# M0_Express_eh_shield.net
KiCad netlist of a schematic drawn in EAGLE
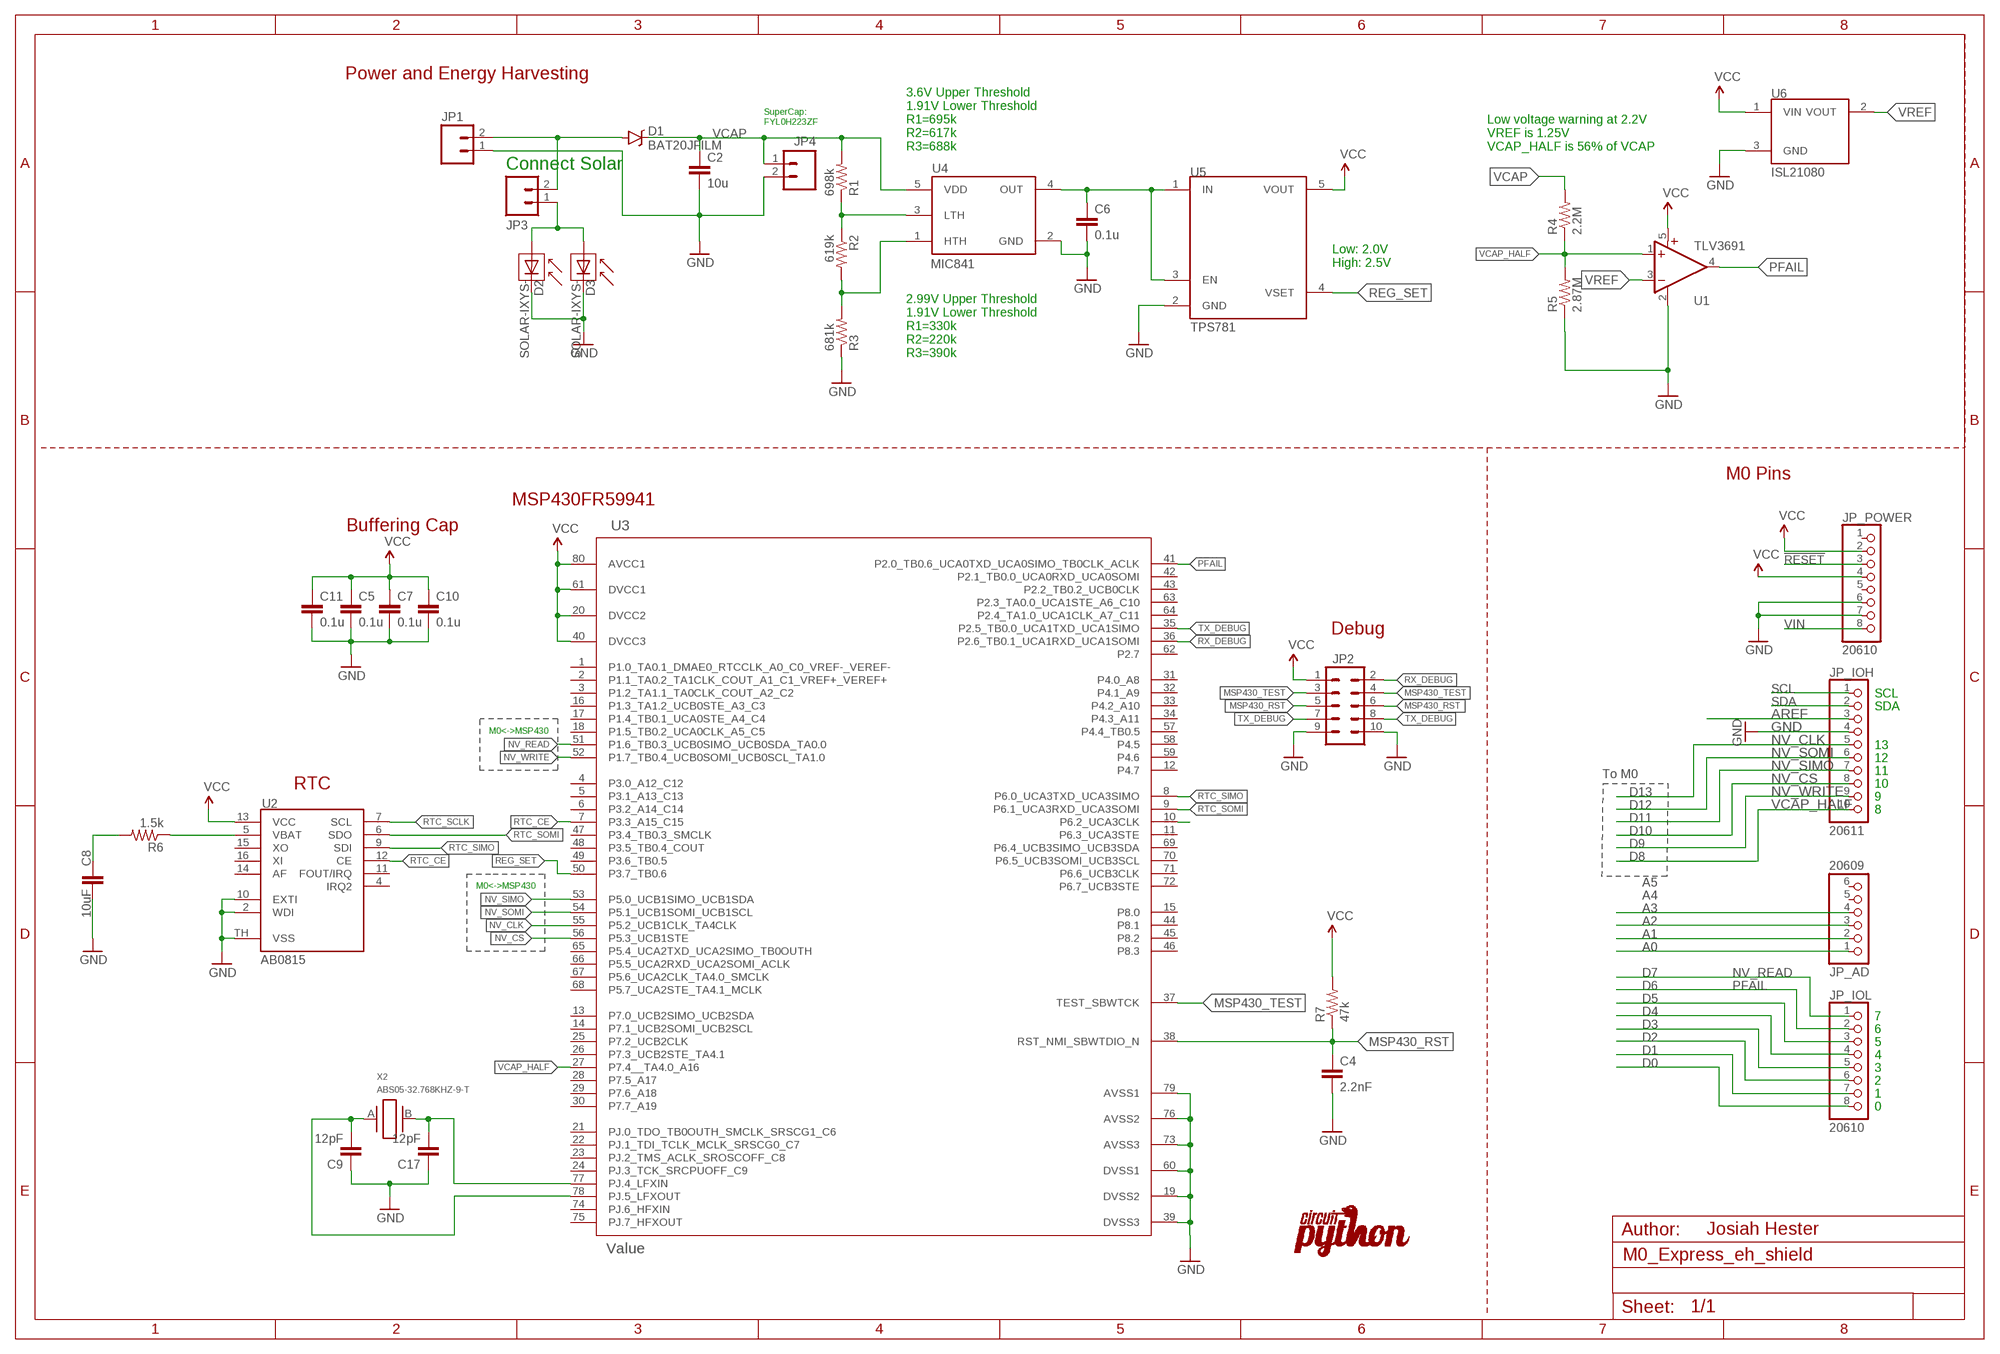
[diagram p0: schematic, sheet 1]

(export (version "E")
  (design (tool "Eeschema 10.0.6"))
  (components
    (comp (ref "C2")
      (value "10u")
      (footprint "eagle-import:0805")
      (libsource (lib "eagle-import") (part "CAP0805"))
    )
    (comp (ref "C4")
      (value "2.2nF")
      (footprint "eagle-import:0603")
      (fields (field (name "MPN") "  06035C222KAT2A"))
      (libsource (lib "eagle-import") (part "C-EU0603"))
    )
    (comp (ref "C5")
      (value "0.1u")
      (footprint "eagle-import:0603")
      (fields (field (name "MPN") "CL10B104KO8NNNC "))
      (libsource (lib "eagle-import") (part "C-EU0603"))
    )
    (comp (ref "C6")
      (value "0.1u")
      (footprint "eagle-import:0603")
      (fields (field (name "MPN") "CL10B104KO8NNNC "))
      (libsource (lib "eagle-import") (part "C-EU0603"))
    )
    (comp (ref "C7")
      (value "0.1u")
      (footprint "eagle-import:0603")
      (fields (field (name "MPN") "CL10B104KO8NNNC "))
      (libsource (lib "eagle-import") (part "C-EU0603"))
    )
    (comp (ref "C8")
      (value "10uF")
      (footprint "eagle-import:0805")
      (libsource (lib "eagle-import") (part "CAP0805"))
    )
    (comp (ref "C9")
      (value "12pF")
      (footprint "eagle-import:0603")
      (fields (field (name "MPN") "CL10C120JB8NNNC"))
      (libsource (lib "eagle-import") (part "C-EU0603"))
    )
    (comp (ref "C10")
      (value "0.1u")
      (footprint "eagle-import:0603")
      (fields (field (name "MPN") "CL10B104KO8NNNC "))
      (libsource (lib "eagle-import") (part "C-EU0603"))
    )
    (comp (ref "C11")
      (value "0.1u")
      (footprint "eagle-import:0603")
      (fields (field (name "MPN") "CL10B104KO8NNNC "))
      (libsource (lib "eagle-import") (part "C-EU0603"))
    )
    (comp (ref "C17")
      (value "12pF")
      (footprint "eagle-import:0603")
      (fields (field (name "MPN") "CL10C120JB8NNNC"))
      (libsource (lib "eagle-import") (part "C-EU0603"))
    )
    (comp (ref "D1")
      (value "BAT20JFILM")
      (footprint "eagle-import:SOD-323")
      (libsource (lib "eagle-import") (part "BAT20JFILM"))
    )
    (comp (ref "D2")
      (value "SOLAR-IXYS-")
      (footprint "eagle-import:SOLARBIT-12X1")
      (fields (field (name "MPN") "KXOB25-02X8F "))
      (libsource (lib "eagle-import") (part "SOLAR-IXYS-"))
    )
    (comp (ref "D3")
      (value "SOLAR-IXYS-")
      (footprint "eagle-import:SOLARBIT-12X1")
      (fields (field (name "MPN") "KXOB25-02X8F "))
      (libsource (lib "eagle-import") (part "SOLAR-IXYS-"))
    )
    (comp (ref "JP1")
      (value "M02LOCK")
      (footprint "eagle-import:1X02_LOCK")
      (libsource (lib "eagle-import") (part "M02LOCK"))
    )
    (comp (ref "JP2")
      (value "M05X21.27MM")
      (footprint "eagle-import:2X5_1.27MM")
      (fields (field (name "MPN") "3220-10-0100-00 "))
      (libsource (lib "eagle-import") (part "M05X21.27MM"))
    )
    (comp (ref "JP3")
      (value "M02LOCK")
      (footprint "eagle-import:1X02_LOCK")
      (libsource (lib "eagle-import") (part "M02LOCK"))
    )
    (comp (ref "JP4")
      (value "M025MM")
      (footprint "eagle-import:SCREWTERMINAL-5MM-2")
      (libsource (lib "eagle-import") (part "M025MM"))
    )
    (comp (ref "JP_AD")
      (value "20609")
      (footprint "eagle-import:1X06_OVALWAVE")
      (libsource (lib "eagle-import") (part "HEADER-1X6OVALWAVE"))
    )
    (comp (ref "JP_IOH")
      (value "20611")
      (footprint "eagle-import:1X10_OVALWAVE")
      (libsource (lib "eagle-import") (part "HEADER-1X10OVALWAVE"))
    )
    (comp (ref "JP_IOL")
      (value "20610")
      (footprint "eagle-import:1X08_OVALWAVE")
      (libsource (lib "eagle-import") (part "HEADER-1X8OVALWAVE"))
    )
    (comp (ref "JP_POWER")
      (value "20610")
      (footprint "eagle-import:1X08_OVALWAVE")
      (libsource (lib "eagle-import") (part "HEADER-1X8OVALWAVE"))
    )
    (comp (ref "R1")
      (value "698k")
      (footprint "eagle-import:0603")
      (fields (field (name "MPN") "RC0603FR-07698KL "))
      (libsource (lib "eagle-import") (part "R-EU0603"))
    )
    (comp (ref "R2")
      (value "619k")
      (footprint "eagle-import:0603")
      (fields (field (name "MPN") "RC0603FR-07619KL "))
      (libsource (lib "eagle-import") (part "R-EU0603"))
    )
    (comp (ref "R3")
      (value "681k")
      (footprint "eagle-import:0603")
      (fields (field (name "MPN") "RMCF0603FT681K "))
      (libsource (lib "eagle-import") (part "R-EU0603"))
    )
    (comp (ref "R4")
      (value "2.2M")
      (footprint "eagle-import:0603")
      (fields (field (name "MPN") "RC0603FR-072M2L "))
      (libsource (lib "eagle-import") (part "R-EU0603"))
    )
    (comp (ref "R5")
      (value "2.87M")
      (footprint "eagle-import:0603")
      (fields (field (name "MPN") "RMCF0603FT2M87"))
      (libsource (lib "eagle-import") (part "R-EU0603"))
    )
    (comp (ref "R6")
      (value "1.5k")
      (footprint "eagle-import:0603")
      (fields (field (name "MPN") "CRG0603F1K5"))
      (libsource (lib "eagle-import") (part "R-EU0603"))
    )
    (comp (ref "R7")
      (value "47k")
      (footprint "eagle-import:0603")
      (fields (field (name "MPN") "CRCW060347K0JNEAC"))
      (libsource (lib "eagle-import") (part "R-EU0603"))
    )
    (comp (ref "U$1")
      (value "LOGO")
      (footprint "eagle-import:CIRCUITPYTHON-LOGO")
      (libsource (lib "eagle-import") (part "LOGO"))
    )
    (comp (ref "U1")
      (value "TLV3691")
      (footprint "eagle-import:SC70-5")
      (fields (field (name "MPN") "TLV3691IDCKR "))
      (libsource (lib "eagle-import") (part "TLV3691"))
    )
    (comp (ref "U2")
      (value "AB0815")
      (footprint "eagle-import:QFN16")
      (fields (field (name "MPN") "AB0815-T3"))
      (libsource (lib "eagle-import") (part "AB0815"))
    )
    (comp (ref "U3")
      (value "Value")
      (footprint "eagle-import:PN0080A_N")
      (fields
        (field (name "MANUFACTURER") "Texas Instruments")
        (field (name "PARTNUMBER") "MSP430FR5994IPNR")
      )
      (libsource (lib "eagle-import") (part "MSP430FR5994IPNR"))
    )
    (comp (ref "U4")
      (value "MIC841")
      (footprint "eagle-import:SC70-5")
      (fields (field (name "MPN") "MIC841HYC5-TR"))
      (libsource (lib "eagle-import") (part "MIC841"))
    )
    (comp (ref "U5")
      (value "TPS781")
      (footprint "eagle-import:DCK_R-PDSO-G5")
      (libsource (lib "eagle-import") (part "TPS781"))
    )
    (comp (ref "U6")
      (value "ISL21080")
      (footprint "eagle-import:SOT-23")
      (fields (field (name "MPN") "ISL21080DIH312Z-TK "))
      (libsource (lib "eagle-import") (part "ISL21080"))
    )
    (comp (ref "X2")
      (value "ABS05-32.768KHZ-9-T")
      (footprint "eagle-import:ABS05")
      (fields (field (name "MPN") "ABS05-32.768KHZ-9-T "))
      (libsource (lib "eagle-import") (part "ABS05-32.768KHZ-9-T"))
    )
  )
  (nets
    (net (code "1") (name "/A0") (class "Default")
      (node (ref "JP_AD") (pin "1") (pinfunction "1_1") (pintype "passive"))
    )
    (net (code "2") (name "/A1") (class "Default")
      (node (ref "JP_AD") (pin "2") (pinfunction "2_2") (pintype "passive"))
    )
    (net (code "3") (name "/A2") (class "Default")
      (node (ref "JP_AD") (pin "3") (pinfunction "3_3") (pintype "passive"))
    )
    (net (code "4") (name "/A3") (class "Default")
      (node (ref "JP_AD") (pin "4") (pinfunction "4_4") (pintype "passive"))
    )
    (net (code "5") (name "/AREF") (class "Default")
      (node (ref "JP_IOH") (pin "3") (pinfunction "3_3") (pintype "passive"))
    )
    (net (code "6") (name "/D0") (class "Default")
      (node (ref "JP_IOL") (pin "8") (pinfunction "8_8") (pintype "passive"))
    )
    (net (code "7") (name "/D1") (class "Default")
      (node (ref "JP_IOL") (pin "7") (pinfunction "7_7") (pintype "passive"))
    )
    (net (code "8") (name "/D2") (class "Default")
      (node (ref "JP_IOL") (pin "6") (pinfunction "6_6") (pintype "passive"))
    )
    (net (code "9") (name "/D3") (class "Default")
      (node (ref "JP_IOL") (pin "5") (pinfunction "5_5") (pintype "passive"))
    )
    (net (code "10") (name "/D4") (class "Default")
      (node (ref "JP_IOL") (pin "4") (pinfunction "4_4") (pintype "passive"))
    )
    (net (code "11") (name "/D5") (class "Default")
      (node (ref "JP_IOL") (pin "3") (pinfunction "3_3") (pintype "passive"))
    )
    (net (code "12") (name "/SCL") (class "Default")
      (node (ref "JP_IOH") (pin "1") (pinfunction "1_1") (pintype "passive"))
    )
    (net (code "13") (name "/SDA") (class "Default")
      (node (ref "JP_IOH") (pin "2") (pinfunction "2_2") (pintype "passive"))
    )
    (net (code "14") (name "/VIN") (class "Default")
      (node (ref "JP_POWER") (pin "8") (pinfunction "8_8") (pintype "passive"))
    )
    (net (code "15") (name "/~{RESET}") (class "Default")
      (node (ref "JP_POWER") (pin "3") (pinfunction "3_3") (pintype "passive"))
    )
    (net (code "16") (name "GND") (class "Default")
      (node (ref "C10") (pin "2") (pinfunction "2_2") (pintype "passive"))
      (node (ref "C11") (pin "2") (pinfunction "2_2") (pintype "passive"))
      (node (ref "C17") (pin "1") (pinfunction "1_1") (pintype "passive"))
      (node (ref "C2") (pin "2") (pinfunction "2_2") (pintype "passive"))
      (node (ref "C4") (pin "2") (pinfunction "2_2") (pintype "passive"))
      (node (ref "C5") (pin "2") (pinfunction "2_2") (pintype "passive"))
      (node (ref "C6") (pin "2") (pinfunction "2_2") (pintype "passive"))
      (node (ref "C7") (pin "2") (pinfunction "2_2") (pintype "passive"))
      (node (ref "C8") (pin "2") (pinfunction "2_2") (pintype "passive"))
      (node (ref "C9") (pin "1") (pinfunction "1_1") (pintype "passive"))
      (node (ref "D2") (pin "-") (pinfunction "C_-") (pintype "passive"))
      (node (ref "D3") (pin "-") (pinfunction "C_-") (pintype "passive"))
      (node (ref "JP1") (pin "1") (pinfunction "1_1") (pintype "passive"))
      (node (ref "JP2") (pin "10") (pinfunction "10_10") (pintype "passive"))
      (node (ref "JP2") (pin "9") (pinfunction "9_9") (pintype "passive"))
      (node (ref "JP4") (pin "2") (pinfunction "2_2") (pintype "passive"))
      (node (ref "JP_IOH") (pin "4") (pinfunction "4_4") (pintype "passive"))
      (node (ref "JP_POWER") (pin "6") (pinfunction "6_6") (pintype "passive"))
      (node (ref "JP_POWER") (pin "7") (pinfunction "7_7") (pintype "passive"))
      (node (ref "R3") (pin "1") (pinfunction "1_1") (pintype "passive"))
      (node (ref "R5") (pin "1") (pinfunction "1_1") (pintype "passive"))
      (node (ref "U1") (pin "2") (pinfunction "GND_2") (pintype "power_in"))
      (node (ref "U2") (pin "10") (pinfunction "EXTI_10") (pintype "bidirectional"))
      (node (ref "U2") (pin "2") (pinfunction "WDI_2") (pintype "bidirectional"))
      (node (ref "U2") (pin "TH") (pinfunction "VSS_TH") (pintype "bidirectional"))
      (node (ref "U3") (pin "19") (pinfunction "DVSS2_19") (pintype "power_in"))
      (node (ref "U3") (pin "39") (pinfunction "DVSS3_39") (pintype "power_in"))
      (node (ref "U3") (pin "60") (pinfunction "DVSS1_60") (pintype "power_in"))
      (node (ref "U3") (pin "73") (pinfunction "AVSS3_73") (pintype "power_in"))
      (node (ref "U3") (pin "76") (pinfunction "AVSS2_76") (pintype "power_in"))
      (node (ref "U3") (pin "79") (pinfunction "AVSS1_79") (pintype "power_in"))
      (node (ref "U4") (pin "2") (pinfunction "GND_2") (pintype "bidirectional"))
      (node (ref "U5") (pin "2") (pinfunction "GND_2") (pintype "bidirectional"))
      (node (ref "U6") (pin "3") (pinfunction "GND_3") (pintype "bidirectional"))
    )
    (net (code "17") (name "MSP430_RST") (class "Default")
      (node (ref "C4") (pin "1") (pinfunction "1_1") (pintype "passive"))
      (node (ref "JP2") (pin "5") (pinfunction "5_5") (pintype "passive"))
      (node (ref "JP2") (pin "6") (pinfunction "6_6") (pintype "passive"))
      (node (ref "R7") (pin "1") (pinfunction "1_1") (pintype "passive"))
      (node (ref "U3") (pin "38") (pinfunction "RST_NMI_SBWTDIO_N_38") (pintype "bidirectional"))
    )
    (net (code "18") (name "MSP430_TEST") (class "Default")
      (node (ref "JP2") (pin "3") (pinfunction "3_3") (pintype "passive"))
      (node (ref "JP2") (pin "4") (pinfunction "4_4") (pintype "passive"))
      (node (ref "U3") (pin "37") (pinfunction "TEST_SBWTCK_37") (pintype "input"))
    )
    (net (code "19") (name "NV_CLK") (class "Default")
      (node (ref "JP_IOH") (pin "5") (pinfunction "5_5") (pintype "passive"))
      (node (ref "U3") (pin "55") (pinfunction "P5.2_UCB1CLK_TA4CLK_55") (pintype "bidirectional"))
    )
    (net (code "20") (name "NV_CS") (class "Default")
      (node (ref "JP_IOH") (pin "8") (pinfunction "8_8") (pintype "passive"))
      (node (ref "U3") (pin "56") (pinfunction "P5.3_UCB1STE_56") (pintype "bidirectional"))
    )
    (net (code "21") (name "NV_READ") (class "Default")
      (node (ref "JP_IOL") (pin "1") (pinfunction "1_1") (pintype "passive"))
      (node (ref "U3") (pin "51") (pinfunction "P1.6_TB0.3_UCB0SIMO_UCB0SDA_TA0.0_51") (pintype "bidirectional"))
    )
    (net (code "22") (name "NV_SIMO") (class "Default")
      (node (ref "JP_IOH") (pin "7") (pinfunction "7_7") (pintype "passive"))
      (node (ref "U3") (pin "53") (pinfunction "P5.0_UCB1SIMO_UCB1SDA_53") (pintype "bidirectional"))
    )
    (net (code "23") (name "NV_SOMI") (class "Default")
      (node (ref "JP_IOH") (pin "6") (pinfunction "6_6") (pintype "passive"))
      (node (ref "U3") (pin "54") (pinfunction "P5.1_UCB1SOMI_UCB1SCL_54") (pintype "bidirectional"))
    )
    (net (code "24") (name "NV_WRITE") (class "Default")
      (node (ref "JP_IOH") (pin "9") (pinfunction "9_9") (pintype "passive"))
      (node (ref "U3") (pin "52") (pinfunction "P1.7_TB0.4_UCB0SOMI_UCB0SCL_TA1.0_52") (pintype "bidirectional"))
    )
    (net (code "25") (name "Net-(C8-Pad1)") (class "Default")
      (node (ref "C8") (pin "1") (pinfunction "1_1") (pintype "passive"))
      (node (ref "R6") (pin "2") (pinfunction "2_2") (pintype "passive"))
    )
    (net (code "26") (name "Net-(D1-PadA)") (class "Default")
      (node (ref "D1") (pin "A") (pinfunction "A_A") (pintype "passive"))
      (node (ref "JP1") (pin "2") (pinfunction "2_2") (pintype "passive"))
      (node (ref "JP3") (pin "2") (pinfunction "2_2") (pintype "passive"))
    )
    (net (code "27") (name "Net-(D2-A)") (class "Default")
      (node (ref "D2") (pin "+") (pinfunction "A_+") (pintype "passive"))
      (node (ref "D3") (pin "+") (pinfunction "A_+") (pintype "passive"))
      (node (ref "JP3") (pin "1") (pinfunction "1_1") (pintype "passive"))
    )
    (net (code "28") (name "Net-(U2-VBAT)") (class "Default")
      (node (ref "R6") (pin "1") (pinfunction "1_1") (pintype "passive"))
      (node (ref "U2") (pin "5") (pinfunction "VBAT_5") (pintype "bidirectional"))
    )
    (net (code "29") (name "Net-(U3-PJ.4_LFXIN)") (class "Default")
      (node (ref "C17") (pin "2") (pinfunction "2_2") (pintype "passive"))
      (node (ref "U3") (pin "77") (pinfunction "PJ.4_LFXIN_77") (pintype "bidirectional"))
      (node (ref "X2") (pin "B") (pinfunction "2_B") (pintype "bidirectional"))
    )
    (net (code "30") (name "Net-(U3-PJ.5_LFXOUT)") (class "Default")
      (node (ref "C9") (pin "2") (pinfunction "2_2") (pintype "passive"))
      (node (ref "U3") (pin "78") (pinfunction "PJ.5_LFXOUT_78") (pintype "bidirectional"))
      (node (ref "X2") (pin "A") (pinfunction "1_A") (pintype "bidirectional"))
    )
    (net (code "31") (name "Net-(U4-HTH)") (class "Default")
      (node (ref "R2") (pin "2") (pinfunction "2_2") (pintype "passive"))
      (node (ref "R3") (pin "2") (pinfunction "2_2") (pintype "passive"))
      (node (ref "U4") (pin "1") (pinfunction "HTH_1") (pintype "bidirectional"))
    )
    (net (code "32") (name "Net-(U4-LTH)") (class "Default")
      (node (ref "R1") (pin "1") (pinfunction "1_1") (pintype "passive"))
      (node (ref "R2") (pin "1") (pinfunction "1_1") (pintype "passive"))
      (node (ref "U4") (pin "3") (pinfunction "LTH_3") (pintype "bidirectional"))
    )
    (net (code "33") (name "Net-(U4-OUT)") (class "Default")
      (node (ref "C6") (pin "1") (pinfunction "1_1") (pintype "passive"))
      (node (ref "U4") (pin "4") (pinfunction "OUT_4") (pintype "bidirectional"))
      (node (ref "U5") (pin "1") (pinfunction "IN_1") (pintype "bidirectional"))
      (node (ref "U5") (pin "3") (pinfunction "EN_3") (pintype "bidirectional"))
    )
    (net (code "34") (name "PFAIL") (class "Default")
      (node (ref "JP_IOL") (pin "2") (pinfunction "2_2") (pintype "passive"))
      (node (ref "U1") (pin "4") (pinfunction "OUT_4") (pintype "output"))
      (node (ref "U3") (pin "41") (pinfunction "P2.0_TB0.6_UCA0TXD_UCA0SIMO_TB0CLK_ACLK_41") (pintype "bidirectional"))
    )
    (net (code "35") (name "REG_SET") (class "Default")
      (node (ref "U3") (pin "50") (pinfunction "P3.7_TB0.6_50") (pintype "bidirectional"))
      (node (ref "U5") (pin "4") (pinfunction "VSET_4") (pintype "bidirectional"))
    )
    (net (code "36") (name "RTC_CE") (class "Default")
      (node (ref "U2") (pin "12") (pinfunction "CE_12") (pintype "bidirectional"))
      (node (ref "U3") (pin "7") (pinfunction "P3.3_A15_C15_7") (pintype "bidirectional"))
    )
    (net (code "37") (name "RTC_SCLK") (class "Default")
      (node (ref "U2") (pin "7") (pinfunction "SCL_7") (pintype "bidirectional"))
      (node (ref "U3") (pin "10") (pinfunction "P6.2_UCA3CLK_10") (pintype "bidirectional"))
    )
    (net (code "38") (name "RTC_SIMO") (class "Default")
      (node (ref "U2") (pin "9") (pinfunction "SDI_9") (pintype "bidirectional"))
      (node (ref "U3") (pin "8") (pinfunction "P6.0_UCA3TXD_UCA3SIMO_8") (pintype "bidirectional"))
    )
    (net (code "39") (name "RTC_SOMI") (class "Default")
      (node (ref "U2") (pin "6") (pinfunction "SDO_6") (pintype "bidirectional"))
      (node (ref "U3") (pin "9") (pinfunction "P6.1_UCA3RXD_UCA3SOMI_9") (pintype "bidirectional"))
    )
    (net (code "40") (name "RX_DEBUG") (class "Default")
      (node (ref "JP2") (pin "2") (pinfunction "2_2") (pintype "passive"))
      (node (ref "U3") (pin "36") (pinfunction "P2.6_TB0.1_UCA1RXD_UCA1SOMI_36") (pintype "bidirectional"))
    )
    (net (code "41") (name "TX_DEBUG") (class "Default")
      (node (ref "JP2") (pin "7") (pinfunction "7_7") (pintype "passive"))
      (node (ref "JP2") (pin "8") (pinfunction "8_8") (pintype "passive"))
      (node (ref "U3") (pin "35") (pinfunction "P2.5_TB0.0_UCA1TXD_UCA1SIMO_35") (pintype "bidirectional"))
    )
    (net (code "42") (name "VCAP") (class "Default")
      (node (ref "C2") (pin "1") (pinfunction "1_1") (pintype "passive"))
      (node (ref "D1") (pin "C") (pinfunction "C_C") (pintype "passive"))
      (node (ref "JP4") (pin "1") (pinfunction "1_1") (pintype "passive"))
      (node (ref "R1") (pin "2") (pinfunction "2_2") (pintype "passive"))
      (node (ref "R4") (pin "2") (pinfunction "2_2") (pintype "passive"))
      (node (ref "U4") (pin "5") (pinfunction "VDD_5") (pintype "bidirectional"))
    )
    (net (code "43") (name "VCAP_HALF") (class "Default")
      (node (ref "JP_IOH") (pin "10") (pinfunction "10_10") (pintype "passive"))
      (node (ref "R4") (pin "1") (pinfunction "1_1") (pintype "passive"))
      (node (ref "R5") (pin "2") (pinfunction "2_2") (pintype "passive"))
      (node (ref "U1") (pin "1") (pinfunction "+IN_1") (pintype "input"))
      (node (ref "U3") (pin "27") (pinfunction "P7.4__TA4.0_A16_27") (pintype "bidirectional"))
    )
    (net (code "44") (name "VCC") (class "Default")
      (node (ref "C10") (pin "1") (pinfunction "1_1") (pintype "passive"))
      (node (ref "C11") (pin "1") (pinfunction "1_1") (pintype "passive"))
      (node (ref "C5") (pin "1") (pinfunction "1_1") (pintype "passive"))
      (node (ref "C7") (pin "1") (pinfunction "1_1") (pintype "passive"))
      (node (ref "JP2") (pin "1") (pinfunction "1_1") (pintype "passive"))
      (node (ref "JP_POWER") (pin "2") (pinfunction "2_2") (pintype "passive"))
      (node (ref "JP_POWER") (pin "4") (pinfunction "4_4") (pintype "passive"))
      (node (ref "R7") (pin "2") (pinfunction "2_2") (pintype "passive"))
      (node (ref "U1") (pin "5") (pinfunction "V+_5") (pintype "power_in"))
      (node (ref "U2") (pin "13") (pinfunction "VCC_13") (pintype "bidirectional"))
      (node (ref "U3") (pin "20") (pinfunction "DVCC2_20") (pintype "power_in"))
      (node (ref "U3") (pin "40") (pinfunction "DVCC3_40") (pintype "power_in"))
      (node (ref "U3") (pin "61") (pinfunction "DVCC1_61") (pintype "power_in"))
      (node (ref "U3") (pin "80") (pinfunction "AVCC1_80") (pintype "power_in"))
      (node (ref "U5") (pin "5") (pinfunction "VOUT_5") (pintype "bidirectional"))
      (node (ref "U6") (pin "1") (pinfunction "VIN_1") (pintype "bidirectional"))
    )
    (net (code "45") (name "VREF") (class "Default")
      (node (ref "U1") (pin "3") (pinfunction "-IN_3") (pintype "input"))
      (node (ref "U6") (pin "2") (pinfunction "VOUT_2") (pintype "bidirectional"))
    )
    (net (code "46") (name "unconnected-(JP_AD-Pad5)") (class "Default")
      (node (ref "JP_AD") (pin "5") (pinfunction "5_5") (pintype "passive"))
    )
    (net (code "47") (name "unconnected-(JP_AD-Pad6)") (class "Default")
      (node (ref "JP_AD") (pin "6") (pinfunction "6_6") (pintype "passive"))
    )
    (net (code "48") (name "unconnected-(JP_POWER-Pad1)") (class "Default")
      (node (ref "JP_POWER") (pin "1") (pinfunction "1_1") (pintype "passive"))
    )
    (net (code "49") (name "unconnected-(JP_POWER-Pad5)") (class "Default")
      (node (ref "JP_POWER") (pin "5") (pinfunction "5_5") (pintype "passive"))
    )
    (net (code "50") (name "unconnected-(U2-AF-Pad14)") (class "Default")
      (node (ref "U2") (pin "14") (pinfunction "AF_14") (pintype "bidirectional"))
    )
    (net (code "51") (name "unconnected-(U2-FOUT{slash}IRQ-Pad11)") (class "Default")
      (node (ref "U2") (pin "11") (pinfunction "FOUT/IRQ_11") (pintype "bidirectional"))
    )
    (net (code "52") (name "unconnected-(U2-IRQ2-Pad4)") (class "Default")
      (node (ref "U2") (pin "4") (pinfunction "IRQ2_4") (pintype "bidirectional"))
    )
    (net (code "53") (name "unconnected-(U2-XI-Pad16)") (class "Default")
      (node (ref "U2") (pin "16") (pinfunction "XI_16") (pintype "bidirectional"))
    )
    (net (code "54") (name "unconnected-(U2-XO-Pad15)") (class "Default")
      (node (ref "U2") (pin "15") (pinfunction "XO_15") (pintype "bidirectional"))
    )
    (net (code "55") (name "unconnected-(U3-P1.0_TA0.1_DMAE0_RTCCLK_A0_C0_VREF-_VEREF--Pad1)") (class "Default")
      (node (ref "U3") (pin "1") (pinfunction "P1.0_TA0.1_DMAE0_RTCCLK_A0_C0_VREF-_VEREF-_1") (pintype "bidirectional"))
    )
    (net (code "56") (name "unconnected-(U3-P1.1_TA0.2_TA1CLK_COUT_A1_C1_VREF+_VEREF+-Pad2)") (class "Default")
      (node (ref "U3") (pin "2") (pinfunction "P1.1_TA0.2_TA1CLK_COUT_A1_C1_VREF+_VEREF+_2") (pintype "bidirectional"))
    )
    (net (code "57") (name "unconnected-(U3-P1.2_TA1.1_TA0CLK_COUT_A2_C2-Pad3)") (class "Default")
      (node (ref "U3") (pin "3") (pinfunction "P1.2_TA1.1_TA0CLK_COUT_A2_C2_3") (pintype "bidirectional"))
    )
    (net (code "58") (name "unconnected-(U3-P1.3_TA1.2_UCB0STE_A3_C3-Pad16)") (class "Default")
      (node (ref "U3") (pin "16") (pinfunction "P1.3_TA1.2_UCB0STE_A3_C3_16") (pintype "bidirectional"))
    )
    (net (code "59") (name "unconnected-(U3-P1.4_TB0.1_UCA0STE_A4_C4-Pad17)") (class "Default")
      (node (ref "U3") (pin "17") (pinfunction "P1.4_TB0.1_UCA0STE_A4_C4_17") (pintype "bidirectional"))
    )
    (net (code "60") (name "unconnected-(U3-P1.5_TB0.2_UCA0CLK_A5_C5-Pad18)") (class "Default")
      (node (ref "U3") (pin "18") (pinfunction "P1.5_TB0.2_UCA0CLK_A5_C5_18") (pintype "bidirectional"))
    )
    (net (code "61") (name "unconnected-(U3-P2.1_TB0.0_UCA0RXD_UCA0SOMI-Pad42)") (class "Default")
      (node (ref "U3") (pin "42") (pinfunction "P2.1_TB0.0_UCA0RXD_UCA0SOMI_42") (pintype "bidirectional"))
    )
    (net (code "62") (name "unconnected-(U3-P2.2_TB0.2_UCB0CLK-Pad43)") (class "Default")
      (node (ref "U3") (pin "43") (pinfunction "P2.2_TB0.2_UCB0CLK_43") (pintype "bidirectional"))
    )
    (net (code "63") (name "unconnected-(U3-P2.3_TA0.0_UCA1STE_A6_C10-Pad63)") (class "Default")
      (node (ref "U3") (pin "63") (pinfunction "P2.3_TA0.0_UCA1STE_A6_C10_63") (pintype "bidirectional"))
    )
    (net (code "64") (name "unconnected-(U3-P2.4_TA1.0_UCA1CLK_A7_C11-Pad64)") (class "Default")
      (node (ref "U3") (pin "64") (pinfunction "P2.4_TA1.0_UCA1CLK_A7_C11_64") (pintype "bidirectional"))
    )
    (net (code "65") (name "unconnected-(U3-P2.7-Pad62)") (class "Default")
      (node (ref "U3") (pin "62") (pinfunction "P2.7_62") (pintype "bidirectional"))
    )
    (net (code "66") (name "unconnected-(U3-P3.0_A12_C12-Pad4)") (class "Default")
      (node (ref "U3") (pin "4") (pinfunction "P3.0_A12_C12_4") (pintype "bidirectional"))
    )
    (net (code "67") (name "unconnected-(U3-P3.1_A13_C13-Pad5)") (class "Default")
      (node (ref "U3") (pin "5") (pinfunction "P3.1_A13_C13_5") (pintype "bidirectional"))
    )
    (net (code "68") (name "unconnected-(U3-P3.2_A14_C14-Pad6)") (class "Default")
      (node (ref "U3") (pin "6") (pinfunction "P3.2_A14_C14_6") (pintype "bidirectional"))
    )
    (net (code "69") (name "unconnected-(U3-P3.4_TB0.3_SMCLK-Pad47)") (class "Default")
      (node (ref "U3") (pin "47") (pinfunction "P3.4_TB0.3_SMCLK_47") (pintype "bidirectional"))
    )
    (net (code "70") (name "unconnected-(U3-P3.5_TB0.4_COUT-Pad48)") (class "Default")
      (node (ref "U3") (pin "48") (pinfunction "P3.5_TB0.4_COUT_48") (pintype "bidirectional"))
    )
    (net (code "71") (name "unconnected-(U3-P3.6_TB0.5-Pad49)") (class "Default")
      (node (ref "U3") (pin "49") (pinfunction "P3.6_TB0.5_49") (pintype "bidirectional"))
    )
    (net (code "72") (name "unconnected-(U3-P4.0_A8-Pad31)") (class "Default")
      (node (ref "U3") (pin "31") (pinfunction "P4.0_A8_31") (pintype "bidirectional"))
    )
    (net (code "73") (name "unconnected-(U3-P4.1_A9-Pad32)") (class "Default")
      (node (ref "U3") (pin "32") (pinfunction "P4.1_A9_32") (pintype "bidirectional"))
    )
    (net (code "74") (name "unconnected-(U3-P4.2_A10-Pad33)") (class "Default")
      (node (ref "U3") (pin "33") (pinfunction "P4.2_A10_33") (pintype "bidirectional"))
    )
    (net (code "75") (name "unconnected-(U3-P4.3_A11-Pad34)") (class "Default")
      (node (ref "U3") (pin "34") (pinfunction "P4.3_A11_34") (pintype "bidirectional"))
    )
    (net (code "76") (name "unconnected-(U3-P4.4_TB0.5-Pad57)") (class "Default")
      (node (ref "U3") (pin "57") (pinfunction "P4.4_TB0.5_57") (pintype "bidirectional"))
    )
    (net (code "77") (name "unconnected-(U3-P4.5-Pad58)") (class "Default")
      (node (ref "U3") (pin "58") (pinfunction "P4.5_58") (pintype "bidirectional"))
    )
    (net (code "78") (name "unconnected-(U3-P4.6-Pad59)") (class "Default")
      (node (ref "U3") (pin "59") (pinfunction "P4.6_59") (pintype "bidirectional"))
    )
    (net (code "79") (name "unconnected-(U3-P4.7-Pad12)") (class "Default")
      (node (ref "U3") (pin "12") (pinfunction "P4.7_12") (pintype "bidirectional"))
    )
    (net (code "80") (name "unconnected-(U3-P5.4_UCA2TXD_UCA2SIMO_TB0OUTH-Pad65)") (class "Default")
      (node (ref "U3") (pin "65") (pinfunction "P5.4_UCA2TXD_UCA2SIMO_TB0OUTH_65") (pintype "bidirectional"))
    )
    (net (code "81") (name "unconnected-(U3-P5.5_UCA2RXD_UCA2SOMI_ACLK-Pad66)") (class "Default")
      (node (ref "U3") (pin "66") (pinfunction "P5.5_UCA2RXD_UCA2SOMI_ACLK_66") (pintype "bidirectional"))
    )
    (net (code "82") (name "unconnected-(U3-P5.6_UCA2CLK_TA4.0_SMCLK-Pad67)") (class "Default")
      (node (ref "U3") (pin "67") (pinfunction "P5.6_UCA2CLK_TA4.0_SMCLK_67") (pintype "bidirectional"))
    )
    (net (code "83") (name "unconnected-(U3-P5.7_UCA2STE_TA4.1_MCLK-Pad68)") (class "Default")
      (node (ref "U3") (pin "68") (pinfunction "P5.7_UCA2STE_TA4.1_MCLK_68") (pintype "bidirectional"))
    )
    (net (code "84") (name "unconnected-(U3-P6.3_UCA3STE-Pad11)") (class "Default")
      (node (ref "U3") (pin "11") (pinfunction "P6.3_UCA3STE_11") (pintype "bidirectional"))
    )
    (net (code "85") (name "unconnected-(U3-P6.4_UCB3SIMO_UCB3SDA-Pad69)") (class "Default")
      (node (ref "U3") (pin "69") (pinfunction "P6.4_UCB3SIMO_UCB3SDA_69") (pintype "bidirectional"))
    )
    (net (code "86") (name "unconnected-(U3-P6.5_UCB3SOMI_UCB3SCL-Pad70)") (class "Default")
      (node (ref "U3") (pin "70") (pinfunction "P6.5_UCB3SOMI_UCB3SCL_70") (pintype "bidirectional"))
    )
    (net (code "87") (name "unconnected-(U3-P6.6_UCB3CLK-Pad71)") (class "Default")
      (node (ref "U3") (pin "71") (pinfunction "P6.6_UCB3CLK_71") (pintype "bidirectional"))
    )
    (net (code "88") (name "unconnected-(U3-P6.7_UCB3STE-Pad72)") (class "Default")
      (node (ref "U3") (pin "72") (pinfunction "P6.7_UCB3STE_72") (pintype "bidirectional"))
    )
    (net (code "89") (name "unconnected-(U3-P7.0_UCB2SIMO_UCB2SDA-Pad13)") (class "Default")
      (node (ref "U3") (pin "13") (pinfunction "P7.0_UCB2SIMO_UCB2SDA_13") (pintype "bidirectional"))
    )
    (net (code "90") (name "unconnected-(U3-P7.1_UCB2SOMI_UCB2SCL-Pad14)") (class "Default")
      (node (ref "U3") (pin "14") (pinfunction "P7.1_UCB2SOMI_UCB2SCL_14") (pintype "bidirectional"))
    )
    (net (code "91") (name "unconnected-(U3-P7.2_UCB2CLK-Pad25)") (class "Default")
      (node (ref "U3") (pin "25") (pinfunction "P7.2_UCB2CLK_25") (pintype "bidirectional"))
    )
    (net (code "92") (name "unconnected-(U3-P7.3_UCB2STE_TA4.1-Pad26)") (class "Default")
      (node (ref "U3") (pin "26") (pinfunction "P7.3_UCB2STE_TA4.1_26") (pintype "bidirectional"))
    )
    (net (code "93") (name "unconnected-(U3-P7.5_A17-Pad28)") (class "Default")
      (node (ref "U3") (pin "28") (pinfunction "P7.5_A17_28") (pintype "bidirectional"))
    )
    (net (code "94") (name "unconnected-(U3-P7.6_A18-Pad29)") (class "Default")
      (node (ref "U3") (pin "29") (pinfunction "P7.6_A18_29") (pintype "bidirectional"))
    )
    (net (code "95") (name "unconnected-(U3-P7.7_A19-Pad30)") (class "Default")
      (node (ref "U3") (pin "30") (pinfunction "P7.7_A19_30") (pintype "bidirectional"))
    )
    (net (code "96") (name "unconnected-(U3-P8.0-Pad15)") (class "Default")
      (node (ref "U3") (pin "15") (pinfunction "P8.0_15") (pintype "bidirectional"))
    )
    (net (code "97") (name "unconnected-(U3-P8.1-Pad44)") (class "Default")
      (node (ref "U3") (pin "44") (pinfunction "P8.1_44") (pintype "bidirectional"))
    )
    (net (code "98") (name "unconnected-(U3-P8.2-Pad45)") (class "Default")
      (node (ref "U3") (pin "45") (pinfunction "P8.2_45") (pintype "bidirectional"))
    )
    (net (code "99") (name "unconnected-(U3-P8.3-Pad46)") (class "Default")
      (node (ref "U3") (pin "46") (pinfunction "P8.3_46") (pintype "bidirectional"))
    )
    (net (code "100") (name "unconnected-(U3-PJ.0_TDO_TB0OUTH_SMCLK_SRSCG1_C6-Pad21)") (class "Default")
      (node (ref "U3") (pin "21") (pinfunction "PJ.0_TDO_TB0OUTH_SMCLK_SRSCG1_C6_21") (pintype "bidirectional"))
    )
    (net (code "101") (name "unconnected-(U3-PJ.1_TDI_TCLK_MCLK_SRSCG0_C7-Pad22)") (class "Default")
      (node (ref "U3") (pin "22") (pinfunction "PJ.1_TDI_TCLK_MCLK_SRSCG0_C7_22") (pintype "bidirectional"))
    )
    (net (code "102") (name "unconnected-(U3-PJ.2_TMS_ACLK_SROSCOFF_C8-Pad23)") (class "Default")
      (node (ref "U3") (pin "23") (pinfunction "PJ.2_TMS_ACLK_SROSCOFF_C8_23") (pintype "bidirectional"))
    )
    (net (code "103") (name "unconnected-(U3-PJ.3_TCK_SRCPUOFF_C9-Pad24)") (class "Default")
      (node (ref "U3") (pin "24") (pinfunction "PJ.3_TCK_SRCPUOFF_C9_24") (pintype "bidirectional"))
    )
    (net (code "104") (name "unconnected-(U3-PJ.6_HFXIN-Pad74)") (class "Default")
      (node (ref "U3") (pin "74") (pinfunction "PJ.6_HFXIN_74") (pintype "bidirectional"))
    )
    (net (code "105") (name "unconnected-(U3-PJ.7_HFXOUT-Pad75)") (class "Default")
      (node (ref "U3") (pin "75") (pinfunction "PJ.7_HFXOUT_75") (pintype "bidirectional"))
    )
  )
)
